# Page_K_B2B_D.net
KiCad netlist of a schematic drawn in Altium Designer
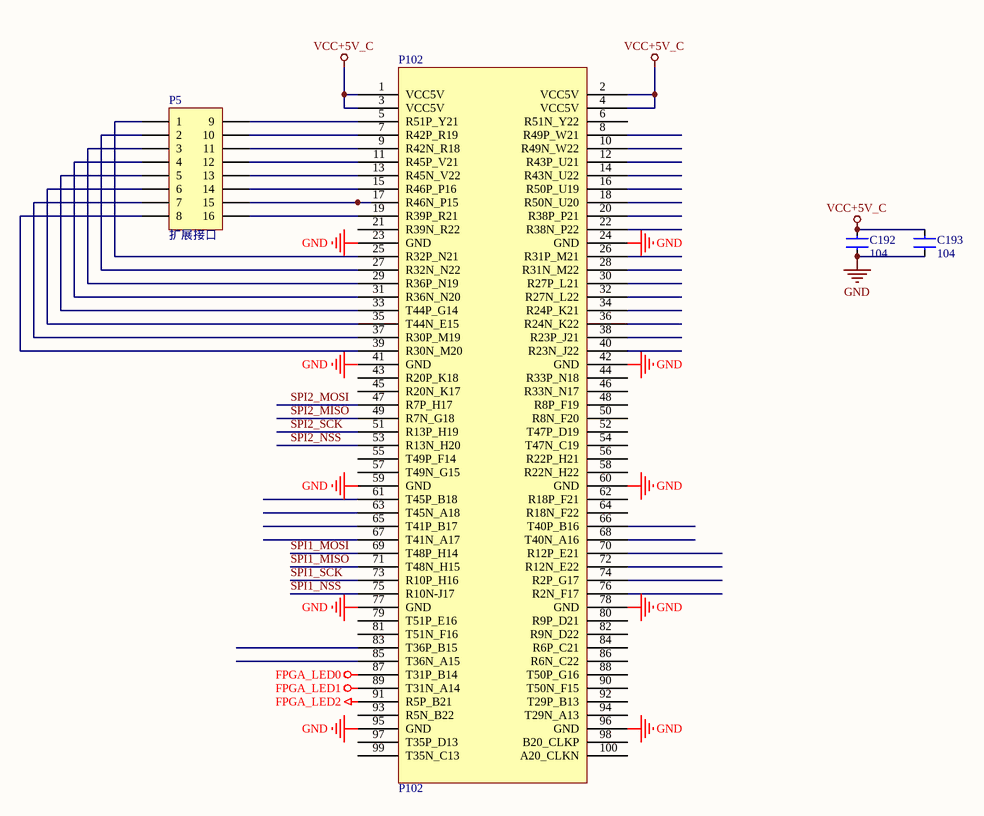
[diagram p0: Page K_B2B_D.SchDoc]

(export (version "E")
  (design (tool "Eeschema 10.0.6"))
  (components
    (comp (ref "C192")
      (value "104")
      (footprint "0603C")
      (description "C-X5R/X7R")
      (libsource (lib "贴片电阻电容") (part "C-X5R/X7R"))
    )
    (comp (ref "C193")
      (value "104")
      (footprint "0603C")
      (description "C-X5R/X7R")
      (libsource (lib "贴片电阻电容") (part "C-X5R/X7R"))
    )
    (comp (ref "P5")
      (value "扩展接口")
      (footprint "HDR2X8_CEN")
      (description "Header, 8-Pin, Dual row")
      (fields (field (name "PUBLISHER") "Altium Limited"))
      (libsource (lib "Miscellaneous Connectors") (part "Header 8X2A"))
    )
    (comp (ref "P102") (value "P102") (footprint "IDC100-05MM-SMD") (libsource (lib "3M") (part "IDC102")))
  )
  (nets
    (net (code "1") (name "/SPI1_MISO") (class "Default")
      (node (ref "P102") (pin "71") (pinfunction "T48N_H15_71") (pintype "passive"))
    )
    (net (code "2") (name "/SPI1_MOSI") (class "Default")
      (node (ref "P102") (pin "69") (pinfunction "T48P_H14_69") (pintype "passive"))
    )
    (net (code "3") (name "/SPI1_NSS") (class "Default")
      (node (ref "P102") (pin "75") (pinfunction "R10N-J17_75") (pintype "passive"))
    )
    (net (code "4") (name "/SPI1_SCK") (class "Default")
      (node (ref "P102") (pin "73") (pinfunction "R10P_H16_73") (pintype "passive"))
    )
    (net (code "5") (name "/SPI2_MISO") (class "Default")
      (node (ref "P102") (pin "49") (pinfunction "R7N_G18_49") (pintype "passive"))
    )
    (net (code "6") (name "/SPI2_MOSI") (class "Default")
      (node (ref "P102") (pin "47") (pinfunction "R7P_H17_47") (pintype "passive"))
    )
    (net (code "7") (name "/SPI2_NSS") (class "Default")
      (node (ref "P102") (pin "53") (pinfunction "R13N_H20_53") (pintype "passive"))
    )
    (net (code "8") (name "/SPI2_SCK") (class "Default")
      (node (ref "P102") (pin "51") (pinfunction "R13P_H19_51") (pintype "passive"))
    )
    (net (code "9") (name "FPGA_LED0") (class "Default")
      (node (ref "P102") (pin "87") (pinfunction "T31P_B14_87") (pintype "passive"))
    )
    (net (code "10") (name "FPGA_LED1") (class "Default")
      (node (ref "P102") (pin "89") (pinfunction "T31N_A14_89") (pintype "passive"))
    )
    (net (code "11") (name "FPGA_LED2") (class "Default")
      (node (ref "P102") (pin "91") (pinfunction "R5P_B21_91") (pintype "passive"))
    )
    (net (code "12") (name "GND") (class "Default")
      (node (ref "C192") (pin "1") (pinfunction "1_1") (pintype "passive"))
      (node (ref "C193") (pin "1") (pinfunction "1_1") (pintype "passive"))
      (node (ref "P102") (pin "23") (pinfunction "GND_23") (pintype "passive"))
      (node (ref "P102") (pin "24") (pinfunction "GND_24") (pintype "passive"))
      (node (ref "P102") (pin "41") (pinfunction "GND_41") (pintype "passive"))
      (node (ref "P102") (pin "42") (pinfunction "GND_42") (pintype "passive"))
      (node (ref "P102") (pin "59") (pinfunction "GND_59") (pintype "passive"))
      (node (ref "P102") (pin "60") (pinfunction "GND_60") (pintype "passive"))
      (node (ref "P102") (pin "77") (pinfunction "GND_77") (pintype "passive"))
      (node (ref "P102") (pin "78") (pinfunction "GND_78") (pintype "passive"))
      (node (ref "P102") (pin "95") (pinfunction "GND_95") (pintype "passive"))
      (node (ref "P102") (pin "96") (pinfunction "GND_96") (pintype "passive"))
    )
    (net (code "13") (name "Net-(P102-R30N_M20)") (class "Default")
      (node (ref "P102") (pin "39") (pinfunction "R30N_M20_39") (pintype "passive"))
      (node (ref "P5") (pin "8") (pinfunction "8_8") (pintype "passive"))
    )
    (net (code "14") (name "Net-(P102-R30P_M19)") (class "Default")
      (node (ref "P102") (pin "37") (pinfunction "R30P_M19_37") (pintype "passive"))
      (node (ref "P5") (pin "7") (pinfunction "7_7") (pintype "passive"))
    )
    (net (code "15") (name "Net-(P102-R32N_N22)") (class "Default")
      (node (ref "P102") (pin "27") (pinfunction "R32N_N22_27") (pintype "passive"))
      (node (ref "P5") (pin "2") (pinfunction "2_2") (pintype "passive"))
    )
    (net (code "16") (name "Net-(P102-R32P_N21)") (class "Default")
      (node (ref "P102") (pin "25") (pinfunction "R32P_N21_25") (pintype "passive"))
      (node (ref "P5") (pin "1") (pinfunction "1_1") (pintype "passive"))
    )
    (net (code "17") (name "Net-(P102-R36N_N20)") (class "Default")
      (node (ref "P102") (pin "31") (pinfunction "R36N_N20_31") (pintype "passive"))
      (node (ref "P5") (pin "4") (pinfunction "4_4") (pintype "passive"))
    )
    (net (code "18") (name "Net-(P102-R36P_N19)") (class "Default")
      (node (ref "P102") (pin "29") (pinfunction "R36P_N19_29") (pintype "passive"))
      (node (ref "P5") (pin "3") (pinfunction "3_3") (pintype "passive"))
    )
    (net (code "19") (name "Net-(P102-R39P_R21)") (class "Default")
      (node (ref "P102") (pin "19") (pinfunction "R39P_R21_19") (pintype "passive"))
      (node (ref "P5") (pin "16") (pinfunction "16_16") (pintype "passive"))
    )
    (net (code "20") (name "Net-(P102-R42N_R18)") (class "Default")
      (node (ref "P102") (pin "9") (pinfunction "R42N_R18_9") (pintype "passive"))
      (node (ref "P5") (pin "11") (pinfunction "11_11") (pintype "passive"))
    )
    (net (code "21") (name "Net-(P102-R42P_R19)") (class "Default")
      (node (ref "P102") (pin "7") (pinfunction "R42P_R19_7") (pintype "passive"))
      (node (ref "P5") (pin "10") (pinfunction "10_10") (pintype "passive"))
    )
    (net (code "22") (name "Net-(P102-R45N_V22)") (class "Default")
      (node (ref "P102") (pin "13") (pinfunction "R45N_V22_13") (pintype "passive"))
      (node (ref "P5") (pin "13") (pinfunction "13_13") (pintype "passive"))
    )
    (net (code "23") (name "Net-(P102-R45P_V21)") (class "Default")
      (node (ref "P102") (pin "11") (pinfunction "R45P_V21_11") (pintype "passive"))
      (node (ref "P5") (pin "12") (pinfunction "12_12") (pintype "passive"))
    )
    (net (code "24") (name "Net-(P102-R46N_P15)") (class "Default")
      (node (ref "P102") (pin "17") (pinfunction "R46N_P15_17") (pintype "passive"))
      (node (ref "P5") (pin "15") (pinfunction "15_15") (pintype "passive"))
    )
    (net (code "25") (name "Net-(P102-R46P_P16)") (class "Default")
      (node (ref "P102") (pin "15") (pinfunction "R46P_P16_15") (pintype "passive"))
      (node (ref "P5") (pin "14") (pinfunction "14_14") (pintype "passive"))
    )
    (net (code "26") (name "Net-(P102-R51P_Y21)") (class "Default")
      (node (ref "P102") (pin "5") (pinfunction "R51P_Y21_5") (pintype "passive"))
      (node (ref "P5") (pin "9") (pinfunction "9_9") (pintype "passive"))
    )
    (net (code "27") (name "Net-(P102-T44N_E15)") (class "Default")
      (node (ref "P102") (pin "35") (pinfunction "T44N_E15_35") (pintype "passive"))
      (node (ref "P5") (pin "6") (pinfunction "6_6") (pintype "passive"))
    )
    (net (code "28") (name "Net-(P102-T44P_G14)") (class "Default")
      (node (ref "P102") (pin "33") (pinfunction "T44P_G14_33") (pintype "passive"))
      (node (ref "P5") (pin "5") (pinfunction "5_5") (pintype "passive"))
    )
    (net (code "29") (name "VCC+5V_C") (class "Default")
      (node (ref "C192") (pin "2") (pinfunction "2_2") (pintype "passive"))
      (node (ref "C193") (pin "2") (pinfunction "2_2") (pintype "passive"))
      (node (ref "P102") (pin "1") (pinfunction "VCC5V_1") (pintype "passive"))
      (node (ref "P102") (pin "2") (pinfunction "VCC5V_2") (pintype "passive"))
      (node (ref "P102") (pin "3") (pinfunction "VCC5V_3") (pintype "passive"))
      (node (ref "P102") (pin "4") (pinfunction "VCC5V_4") (pintype "passive"))
    )
    (net (code "30") (name "unconnected-(P102-A20_CLKN-Pad100)") (class "Default")
      (node (ref "P102") (pin "100") (pinfunction "A20_CLKN_100") (pintype "passive"))
    )
    (net (code "31") (name "unconnected-(P102-B20_CLKP-Pad98)") (class "Default")
      (node (ref "P102") (pin "98") (pinfunction "B20_CLKP_98") (pintype "passive"))
    )
    (net (code "32") (name "unconnected-(P102-R2N_F17-Pad76)") (class "Default")
      (node (ref "P102") (pin "76") (pinfunction "R2N_F17_76") (pintype "passive"))
    )
    (net (code "33") (name "unconnected-(P102-R2P_G17-Pad74)") (class "Default")
      (node (ref "P102") (pin "74") (pinfunction "R2P_G17_74") (pintype "passive"))
    )
    (net (code "34") (name "unconnected-(P102-R5N_B22-Pad93)") (class "Default")
      (node (ref "P102") (pin "93") (pinfunction "R5N_B22_93") (pintype "passive"))
    )
    (net (code "35") (name "unconnected-(P102-R6N_C22-Pad86)") (class "Default")
      (node (ref "P102") (pin "86") (pinfunction "R6N_C22_86") (pintype "passive"))
    )
    (net (code "36") (name "unconnected-(P102-R6P_C21-Pad84)") (class "Default")
      (node (ref "P102") (pin "84") (pinfunction "R6P_C21_84") (pintype "passive"))
    )
    (net (code "37") (name "unconnected-(P102-R8N_F20-Pad50)") (class "Default")
      (node (ref "P102") (pin "50") (pinfunction "R8N_F20_50") (pintype "passive"))
    )
    (net (code "38") (name "unconnected-(P102-R8P_F19-Pad48)") (class "Default")
      (node (ref "P102") (pin "48") (pinfunction "R8P_F19_48") (pintype "passive"))
    )
    (net (code "39") (name "unconnected-(P102-R9N_D22-Pad82)") (class "Default")
      (node (ref "P102") (pin "82") (pinfunction "R9N_D22_82") (pintype "passive"))
    )
    (net (code "40") (name "unconnected-(P102-R9P_D21-Pad80)") (class "Default")
      (node (ref "P102") (pin "80") (pinfunction "R9P_D21_80") (pintype "passive"))
    )
    (net (code "41") (name "unconnected-(P102-R12N_E22-Pad72)") (class "Default")
      (node (ref "P102") (pin "72") (pinfunction "R12N_E22_72") (pintype "passive"))
    )
    (net (code "42") (name "unconnected-(P102-R12P_E21-Pad70)") (class "Default")
      (node (ref "P102") (pin "70") (pinfunction "R12P_E21_70") (pintype "passive"))
    )
    (net (code "43") (name "unconnected-(P102-R18N_F22-Pad64)") (class "Default")
      (node (ref "P102") (pin "64") (pinfunction "R18N_F22_64") (pintype "passive"))
    )
    (net (code "44") (name "unconnected-(P102-R18P_F21-Pad62)") (class "Default")
      (node (ref "P102") (pin "62") (pinfunction "R18P_F21_62") (pintype "passive"))
    )
    (net (code "45") (name "unconnected-(P102-R20N_K17-Pad45)") (class "Default")
      (node (ref "P102") (pin "45") (pinfunction "R20N_K17_45") (pintype "passive"))
    )
    (net (code "46") (name "unconnected-(P102-R20P_K18-Pad43)") (class "Default")
      (node (ref "P102") (pin "43") (pinfunction "R20P_K18_43") (pintype "passive"))
    )
    (net (code "47") (name "unconnected-(P102-R22N_H22-Pad58)") (class "Default")
      (node (ref "P102") (pin "58") (pinfunction "R22N_H22_58") (pintype "passive"))
    )
    (net (code "48") (name "unconnected-(P102-R22P_H21-Pad56)") (class "Default")
      (node (ref "P102") (pin "56") (pinfunction "R22P_H21_56") (pintype "passive"))
    )
    (net (code "49") (name "unconnected-(P102-R23N_J22-Pad40)") (class "Default")
      (node (ref "P102") (pin "40") (pinfunction "R23N_J22_40") (pintype "passive"))
    )
    (net (code "50") (name "unconnected-(P102-R23P_J21-Pad38)") (class "Default")
      (node (ref "P102") (pin "38") (pinfunction "R23P_J21_38") (pintype "passive"))
    )
    (net (code "51") (name "unconnected-(P102-R24N_K22-Pad36)") (class "Default")
      (node (ref "P102") (pin "36") (pinfunction "R24N_K22_36") (pintype "passive"))
    )
    (net (code "52") (name "unconnected-(P102-R24P_K21-Pad34)") (class "Default")
      (node (ref "P102") (pin "34") (pinfunction "R24P_K21_34") (pintype "passive"))
    )
    (net (code "53") (name "unconnected-(P102-R27N_L22-Pad32)") (class "Default")
      (node (ref "P102") (pin "32") (pinfunction "R27N_L22_32") (pintype "passive"))
    )
    (net (code "54") (name "unconnected-(P102-R27P_L21-Pad30)") (class "Default")
      (node (ref "P102") (pin "30") (pinfunction "R27P_L21_30") (pintype "passive"))
    )
    (net (code "55") (name "unconnected-(P102-R31N_M22-Pad28)") (class "Default")
      (node (ref "P102") (pin "28") (pinfunction "R31N_M22_28") (pintype "passive"))
    )
    (net (code "56") (name "unconnected-(P102-R31P_M21-Pad26)") (class "Default")
      (node (ref "P102") (pin "26") (pinfunction "R31P_M21_26") (pintype "passive"))
    )
    (net (code "57") (name "unconnected-(P102-R33N_N17-Pad46)") (class "Default")
      (node (ref "P102") (pin "46") (pinfunction "R33N_N17_46") (pintype "passive"))
    )
    (net (code "58") (name "unconnected-(P102-R33P_N18-Pad44)") (class "Default")
      (node (ref "P102") (pin "44") (pinfunction "R33P_N18_44") (pintype "passive"))
    )
    (net (code "59") (name "unconnected-(P102-R38N_P22-Pad22)") (class "Default")
      (node (ref "P102") (pin "22") (pinfunction "R38N_P22_22") (pintype "passive"))
    )
    (net (code "60") (name "unconnected-(P102-R38P_P21-Pad20)") (class "Default")
      (node (ref "P102") (pin "20") (pinfunction "R38P_P21_20") (pintype "passive"))
    )
    (net (code "61") (name "unconnected-(P102-R39N_R22-Pad21)") (class "Default")
      (node (ref "P102") (pin "21") (pinfunction "R39N_R22_21") (pintype "passive"))
    )
    (net (code "62") (name "unconnected-(P102-R43N_U22-Pad14)") (class "Default")
      (node (ref "P102") (pin "14") (pinfunction "R43N_U22_14") (pintype "passive"))
    )
    (net (code "63") (name "unconnected-(P102-R43P_U21-Pad12)") (class "Default")
      (node (ref "P102") (pin "12") (pinfunction "R43P_U21_12") (pintype "passive"))
    )
    (net (code "64") (name "unconnected-(P102-R49N_W22-Pad10)") (class "Default")
      (node (ref "P102") (pin "10") (pinfunction "R49N_W22_10") (pintype "passive"))
    )
    (net (code "65") (name "unconnected-(P102-R49P_W21-Pad8)") (class "Default")
      (node (ref "P102") (pin "8") (pinfunction "R49P_W21_8") (pintype "passive"))
    )
    (net (code "66") (name "unconnected-(P102-R50N_U20-Pad18)") (class "Default")
      (node (ref "P102") (pin "18") (pinfunction "R50N_U20_18") (pintype "passive"))
    )
    (net (code "67") (name "unconnected-(P102-R50P_U19-Pad16)") (class "Default")
      (node (ref "P102") (pin "16") (pinfunction "R50P_U19_16") (pintype "passive"))
    )
    (net (code "68") (name "unconnected-(P102-R51N_Y22-Pad6)") (class "Default")
      (node (ref "P102") (pin "6") (pinfunction "R51N_Y22_6") (pintype "passive"))
    )
    (net (code "69") (name "unconnected-(P102-T29N_A13-Pad94)") (class "Default")
      (node (ref "P102") (pin "94") (pinfunction "T29N_A13_94") (pintype "passive"))
    )
    (net (code "70") (name "unconnected-(P102-T29P_B13-Pad92)") (class "Default")
      (node (ref "P102") (pin "92") (pinfunction "T29P_B13_92") (pintype "passive"))
    )
    (net (code "71") (name "unconnected-(P102-T35N_C13-Pad99)") (class "Default")
      (node (ref "P102") (pin "99") (pinfunction "T35N_C13_99") (pintype "passive"))
    )
    (net (code "72") (name "unconnected-(P102-T35P_D13-Pad97)") (class "Default")
      (node (ref "P102") (pin "97") (pinfunction "T35P_D13_97") (pintype "passive"))
    )
    (net (code "73") (name "unconnected-(P102-T36N_A15-Pad85)") (class "Default")
      (node (ref "P102") (pin "85") (pinfunction "T36N_A15_85") (pintype "passive"))
    )
    (net (code "74") (name "unconnected-(P102-T36P_B15-Pad83)") (class "Default")
      (node (ref "P102") (pin "83") (pinfunction "T36P_B15_83") (pintype "passive"))
    )
    (net (code "75") (name "unconnected-(P102-T40N_A16-Pad68)") (class "Default")
      (node (ref "P102") (pin "68") (pinfunction "T40N_A16_68") (pintype "passive"))
    )
    (net (code "76") (name "unconnected-(P102-T40P_B16-Pad66)") (class "Default")
      (node (ref "P102") (pin "66") (pinfunction "T40P_B16_66") (pintype "passive"))
    )
    (net (code "77") (name "unconnected-(P102-T41N_A17-Pad67)") (class "Default")
      (node (ref "P102") (pin "67") (pinfunction "T41N_A17_67") (pintype "passive"))
    )
    (net (code "78") (name "unconnected-(P102-T41P_B17-Pad65)") (class "Default")
      (node (ref "P102") (pin "65") (pinfunction "T41P_B17_65") (pintype "passive"))
    )
    (net (code "79") (name "unconnected-(P102-T45N_A18-Pad63)") (class "Default")
      (node (ref "P102") (pin "63") (pinfunction "T45N_A18_63") (pintype "passive"))
    )
    (net (code "80") (name "unconnected-(P102-T45P_B18-Pad61)") (class "Default")
      (node (ref "P102") (pin "61") (pinfunction "T45P_B18_61") (pintype "passive"))
    )
    (net (code "81") (name "unconnected-(P102-T47N_C19-Pad54)") (class "Default")
      (node (ref "P102") (pin "54") (pinfunction "T47N_C19_54") (pintype "passive"))
    )
    (net (code "82") (name "unconnected-(P102-T47P_D19-Pad52)") (class "Default")
      (node (ref "P102") (pin "52") (pinfunction "T47P_D19_52") (pintype "passive"))
    )
    (net (code "83") (name "unconnected-(P102-T49N_G15-Pad57)") (class "Default")
      (node (ref "P102") (pin "57") (pinfunction "T49N_G15_57") (pintype "passive"))
    )
    (net (code "84") (name "unconnected-(P102-T49P_F14-Pad55)") (class "Default")
      (node (ref "P102") (pin "55") (pinfunction "T49P_F14_55") (pintype "passive"))
    )
    (net (code "85") (name "unconnected-(P102-T50N_F15-Pad90)") (class "Default")
      (node (ref "P102") (pin "90") (pinfunction "T50N_F15_90") (pintype "passive"))
    )
    (net (code "86") (name "unconnected-(P102-T50P_G16-Pad88)") (class "Default")
      (node (ref "P102") (pin "88") (pinfunction "T50P_G16_88") (pintype "passive"))
    )
    (net (code "87") (name "unconnected-(P102-T51N_F16-Pad81)") (class "Default")
      (node (ref "P102") (pin "81") (pinfunction "T51N_F16_81") (pintype "passive"))
    )
    (net (code "88") (name "unconnected-(P102-T51P_E16-Pad79)") (class "Default")
      (node (ref "P102") (pin "79") (pinfunction "T51P_E16_79") (pintype "passive"))
    )
  )
)
